# sch_power.net
KiCad netlist of a schematic drawn in Altium Designer
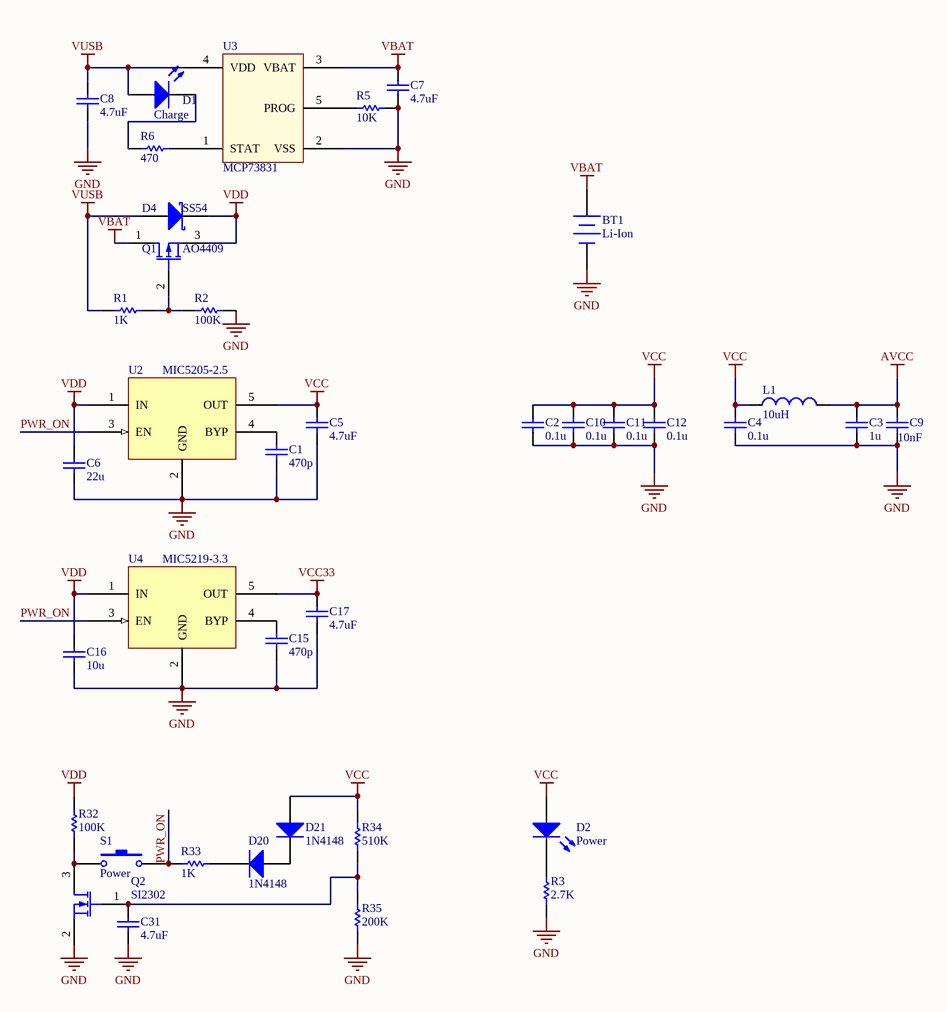
[diagram p0: sch_power.SchDoc]

(export (version "E")
  (design (tool "Eeschema 10.0.6"))
  (components
    (comp (ref "BT1")
      (value "Li-Ion")
      (footprint "HDR1X2")
      (description "Multicell Battery")
      (fields (field (name "PUBLISHER") "Altium Limited"))
      (libsource (lib "Miscellaneous Devices") (part "Battery"))
    )
    (comp (ref "C1")
      (value "470p")
      (footprint "C-1608[0603]")
      (description "Capacitor (Semiconductor SIM Model)")
      (fields (field (name "Comment") "Cap Semi") (field (name "PUBLISHER") "Altium Limited"))
      (libsource (lib "Miscellaneous Devices") (part "Cap Semi"))
    )
    (comp (ref "C2")
      (value "0.1u")
      (footprint "C-1608[0603]")
      (description "Capacitor (Semiconductor SIM Model)")
      (fields (field (name "Comment") "Cap Semi") (field (name "PUBLISHER") "Altium Limited"))
      (libsource (lib "Miscellaneous Devices") (part "Cap Semi"))
    )
    (comp (ref "C3")
      (value "1u")
      (footprint "C-1608[0603]")
      (description "Capacitor (Semiconductor SIM Model)")
      (fields (field (name "Comment") "Cap Semi") (field (name "PUBLISHER") "Altium Limited"))
      (libsource (lib "Miscellaneous Devices") (part "Cap Semi"))
    )
    (comp (ref "C4")
      (value "0.1u")
      (footprint "C-1608[0603]")
      (description "Capacitor (Semiconductor SIM Model)")
      (fields (field (name "Comment") "Cap Semi") (field (name "PUBLISHER") "Altium Limited"))
      (libsource (lib "Miscellaneous Devices") (part "Cap Semi"))
    )
    (comp (ref "C5")
      (value "4.7uF")
      (footprint "C-1608[0603]")
      (description "Capacitor (Semiconductor SIM Model)")
      (fields (field (name "Comment") "Cap Semi") (field (name "PUBLISHER") "Altium Limited"))
      (libsource (lib "Miscellaneous Devices") (part "Cap Semi"))
    )
    (comp (ref "C6")
      (value "22u")
      (footprint "C-2012[0805]")
      (description "Capacitor (Semiconductor SIM Model)")
      (fields (field (name "Comment") "Cap Semi") (field (name "PUBLISHER") "Altium Limited"))
      (libsource (lib "Miscellaneous Devices") (part "Cap Semi"))
    )
    (comp (ref "C7")
      (value "4.7uF")
      (footprint "C-1608[0603]")
      (description "Capacitor (Semiconductor SIM Model)")
      (fields (field (name "Comment") "Cap Semi") (field (name "PUBLISHER") "Altium Limited"))
      (libsource (lib "Miscellaneous Devices") (part "Cap Semi"))
    )
    (comp (ref "C8")
      (value "4.7uF")
      (footprint "C-1608[0603]")
      (description "Capacitor (Semiconductor SIM Model)")
      (fields (field (name "Comment") "Cap Semi") (field (name "PUBLISHER") "Altium Limited"))
      (libsource (lib "Miscellaneous Devices") (part "Cap Semi"))
    )
    (comp (ref "C9")
      (value "10nF")
      (footprint "C-1608[0603]")
      (description "Capacitor (Semiconductor SIM Model)")
      (fields (field (name "Comment") "Cap Semi") (field (name "PUBLISHER") "Altium Limited"))
      (libsource (lib "Miscellaneous Devices") (part "Cap Semi"))
    )
    (comp (ref "C10")
      (value "0.1u")
      (footprint "C-1608[0603]")
      (description "Capacitor (Semiconductor SIM Model)")
      (fields (field (name "Comment") "Cap Semi") (field (name "PUBLISHER") "Altium Limited"))
      (libsource (lib "Miscellaneous Devices") (part "Cap Semi"))
    )
    (comp (ref "C11")
      (value "0.1u")
      (footprint "C-1608[0603]")
      (description "Capacitor (Semiconductor SIM Model)")
      (fields (field (name "Comment") "Cap Semi") (field (name "PUBLISHER") "Altium Limited"))
      (libsource (lib "Miscellaneous Devices") (part "Cap Semi"))
    )
    (comp (ref "C12")
      (value "0.1u")
      (footprint "C-1608[0603]")
      (description "Capacitor (Semiconductor SIM Model)")
      (fields (field (name "Comment") "Cap Semi") (field (name "PUBLISHER") "Altium Limited"))
      (libsource (lib "Miscellaneous Devices") (part "Cap Semi"))
    )
    (comp (ref "C15")
      (value "470p")
      (footprint "C-1608[0603]")
      (description "Capacitor (Semiconductor SIM Model)")
      (fields (field (name "Comment") "Cap Semi") (field (name "PUBLISHER") "Altium Limited"))
      (libsource (lib "Miscellaneous Devices") (part "Cap Semi"))
    )
    (comp (ref "C16")
      (value "10u")
      (footprint "C-2012[0805]")
      (description "Capacitor (Semiconductor SIM Model)")
      (fields (field (name "Comment") "Cap Semi") (field (name "PUBLISHER") "Altium Limited"))
      (libsource (lib "Miscellaneous Devices") (part "Cap Semi"))
    )
    (comp (ref "C17")
      (value "4.7uF")
      (footprint "C-1608[0603]")
      (description "Capacitor (Semiconductor SIM Model)")
      (fields (field (name "Comment") "Cap Semi") (field (name "PUBLISHER") "Altium Limited"))
      (libsource (lib "Miscellaneous Devices") (part "Cap Semi"))
    )
    (comp (ref "C31")
      (value "4.7uF")
      (footprint "C-1608[0603]")
      (description "Capacitor (Semiconductor SIM Model)")
      (fields (field (name "Comment") "Cap Semi") (field (name "PUBLISHER") "Altium Limited"))
      (libsource (lib "Miscellaneous Devices") (part "Cap Semi"))
    )
    (comp (ref "D1")
      (value "Charge")
      (footprint "LED-1608[0603]-R")
      (description "Typical RED, GREEN, YELLOW, AMBER GaAs LED")
      (fields (field (name "PUBLISHER") "Altium Limited"))
      (libsource (lib "Miscellaneous Devices") (part "LED2"))
    )
    (comp (ref "D2")
      (value "Power")
      (footprint "LED-1608[0603]-G")
      (description "Typical RED, GREEN, YELLOW, AMBER GaAs LED")
      (fields (field (name "PUBLISHER") "Altium Limited"))
      (libsource (lib "Miscellaneous Devices") (part "LED2"))
    )
    (comp (ref "D4")
      (value "SS54")
      (footprint "general:DO-214AA")
      (description "Schottky Diode")
      (fields (field (name "PUBLISHER") "Altium Limited"))
      (libsource (lib "Miscellaneous Devices") (part "D Schottky"))
    )
    (comp (ref "D20")
      (value "1N4148")
      (footprint "SOD80C")
      (description "High Conductance Fast Diode")
      (fields (field (name "PUBLISHER") "Altium Limited"))
      (libsource (lib "Miscellaneous Devices") (part "Diode 1N4148"))
    )
    (comp (ref "D21")
      (value "1N4148")
      (footprint "SOD80C")
      (description "High Conductance Fast Diode")
      (fields (field (name "PUBLISHER") "Altium Limited"))
      (libsource (lib "Miscellaneous Devices") (part "Diode 1N4148"))
    )
    (comp (ref "L1")
      (value "10uH")
      (footprint "L-1608[0603]")
      (description "Inductor")
      (fields (field (name "PUBLISHER") "Altium Limited"))
      (libsource (lib "Miscellaneous Devices") (part "Inductor"))
    )
    (comp (ref "Q1")
      (value "AO4409")
      (footprint "SOP8-MOS")
      (description "P-Channel MOSFET")
      (fields (field (name "PUBLISHER") "Altium Limited"))
      (libsource (lib "Miscellaneous Devices") (part "MOSFET-P"))
    )
    (comp (ref "Q2")
      (value "SI2302")
      (footprint "SOT23B")
      (description "N-Channel MOSFET")
      (fields (field (name "PUBLISHER") "Altium Limited"))
      (libsource (lib "general") (part "SI2302"))
    )
    (comp (ref "R1")
      (value "1K")
      (footprint "R-1608[0603]")
      (description "Semiconductor Resistor")
      (fields (field (name "Comment") "Res Semi") (field (name "PUBLISHER") "Altium Limited"))
      (libsource (lib "Miscellaneous Devices") (part "Res Semi"))
    )
    (comp (ref "R2")
      (value "100K")
      (footprint "R-1608[0603]")
      (description "Semiconductor Resistor")
      (fields (field (name "Comment") "Res Semi") (field (name "PUBLISHER") "Altium Limited"))
      (libsource (lib "Miscellaneous Devices") (part "Res Semi"))
    )
    (comp (ref "R3")
      (value "2.7K")
      (footprint "R-1608[0603]")
      (description "Semiconductor Resistor")
      (fields (field (name "Comment") "Res Semi") (field (name "PUBLISHER") "Altium Limited"))
      (libsource (lib "Miscellaneous Devices") (part "Res Semi"))
    )
    (comp (ref "R5")
      (value "10K")
      (footprint "R-1608[0603]")
      (description "Semiconductor Resistor")
      (fields (field (name "Comment") "Res Semi") (field (name "PUBLISHER") "Altium Limited"))
      (libsource (lib "Miscellaneous Devices") (part "Res Semi"))
    )
    (comp (ref "R6")
      (value "470")
      (footprint "R-1608[0603]")
      (description "Semiconductor Resistor")
      (fields (field (name "Comment") "Res Semi") (field (name "PUBLISHER") "Altium Limited"))
      (libsource (lib "Miscellaneous Devices") (part "Res Semi"))
    )
    (comp (ref "R32")
      (value "100K")
      (footprint "R-1608[0603]")
      (description "Semiconductor Resistor")
      (fields (field (name "Comment") "Res Semi") (field (name "PUBLISHER") "Altium Limited"))
      (libsource (lib "Miscellaneous Devices") (part "Res Semi"))
    )
    (comp (ref "R33")
      (value "1K")
      (footprint "R-1608[0603]")
      (description "Semiconductor Resistor")
      (fields (field (name "Comment") "Res Semi") (field (name "PUBLISHER") "Altium Limited"))
      (libsource (lib "Miscellaneous Devices") (part "Res Semi"))
    )
    (comp (ref "R34")
      (value "510K")
      (footprint "R-1608[0603]")
      (description "Semiconductor Resistor")
      (fields (field (name "Comment") "Res Semi") (field (name "PUBLISHER") "Altium Limited"))
      (libsource (lib "Miscellaneous Devices") (part "Res Semi"))
    )
    (comp (ref "R35")
      (value "200K")
      (footprint "R-1608[0603]")
      (description "Semiconductor Resistor")
      (fields (field (name "Comment") "Res Semi") (field (name "PUBLISHER") "Altium Limited"))
      (libsource (lib "Miscellaneous Devices") (part "Res Semi"))
    )
    (comp (ref "S1")
      (value "Power")
      (footprint "TS-015")
      (description "Switch")
      (fields (field (name "PUBLISHER") "Altium Limited"))
      (libsource (lib "Miscellaneous Devices") (part "SW-PB"))
    )
    (comp (ref "U2")
      (value "MIC5205-2.5")
      (footprint "SOT23-5")
      (description "500mA-Peak Output LDO Regulator")
      (libsource (lib "Schlib1") (part "MIC5219"))
    )
    (comp (ref "U3")
      (value "MCP73831")
      (footprint "SOT23-5")
      (description "Miniature Single-Cell, Fully Integrated Li-Ion, Li-Polymer Charge Management Controllers")
      (libsource (lib "MCP73831") (part "MCP73831"))
    )
    (comp (ref "U4")
      (value "MIC5219-3.3")
      (footprint "SOT23-5")
      (description "500mA-Peak Output LDO Regulator")
      (libsource (lib "Schlib1") (part "MIC5219"))
    )
  )
  (nets
    (net (code "1") (name "/PWR_ON") (class "Default")
      (node (ref "R33") (pin "2") (pinfunction "2_2") (pintype "passive"))
      (node (ref "S1") (pin "2") (pinfunction "2_2") (pintype "passive"))
      (node (ref "U2") (pin "3") (pinfunction "EN_3") (pintype "input"))
      (node (ref "U4") (pin "3") (pinfunction "EN_3") (pintype "input"))
    )
    (net (code "2") (name "AVCC") (class "Default")
      (node (ref "C3") (pin "2") (pinfunction "2_2") (pintype "passive"))
      (node (ref "C9") (pin "2") (pinfunction "2_2") (pintype "passive"))
      (node (ref "L1") (pin "2") (pinfunction "2_2") (pintype "passive"))
    )
    (net (code "3") (name "GND") (class "Default")
      (node (ref "BT1") (pin "2") (pinfunction "-_2") (pintype "passive"))
      (node (ref "C1") (pin "2") (pinfunction "2_2") (pintype "passive"))
      (node (ref "C10") (pin "1") (pinfunction "1_1") (pintype "passive"))
      (node (ref "C11") (pin "1") (pinfunction "1_1") (pintype "passive"))
      (node (ref "C12") (pin "1") (pinfunction "1_1") (pintype "passive"))
      (node (ref "C15") (pin "2") (pinfunction "2_2") (pintype "passive"))
      (node (ref "C16") (pin "2") (pinfunction "2_2") (pintype "passive"))
      (node (ref "C17") (pin "2") (pinfunction "2_2") (pintype "passive"))
      (node (ref "C2") (pin "1") (pinfunction "1_1") (pintype "passive"))
      (node (ref "C3") (pin "1") (pinfunction "1_1") (pintype "passive"))
      (node (ref "C31") (pin "1") (pinfunction "1_1") (pintype "passive"))
      (node (ref "C4") (pin "1") (pinfunction "1_1") (pintype "passive"))
      (node (ref "C5") (pin "2") (pinfunction "2_2") (pintype "passive"))
      (node (ref "C6") (pin "2") (pinfunction "2_2") (pintype "passive"))
      (node (ref "C7") (pin "1") (pinfunction "1_1") (pintype "passive"))
      (node (ref "C8") (pin "1") (pinfunction "1_1") (pintype "passive"))
      (node (ref "C9") (pin "1") (pinfunction "1_1") (pintype "passive"))
      (node (ref "Q2") (pin "2") (pinfunction "S_2") (pintype "passive"))
      (node (ref "R2") (pin "2") (pinfunction "2_2") (pintype "passive"))
      (node (ref "R3") (pin "2") (pinfunction "2_2") (pintype "passive"))
      (node (ref "R35") (pin "1") (pinfunction "1_1") (pintype "passive"))
      (node (ref "R5") (pin "1") (pinfunction "1_1") (pintype "passive"))
      (node (ref "U2") (pin "2") (pinfunction "GND_2") (pintype "passive"))
      (node (ref "U3") (pin "2") (pinfunction "VSS_2") (pintype "passive"))
      (node (ref "U4") (pin "2") (pinfunction "GND_2") (pintype "passive"))
    )
    (net (code "4") (name "Net-(D1-K)") (class "Default")
      (node (ref "D1") (pin "2") (pinfunction "K_2") (pintype "passive"))
      (node (ref "R6") (pin "1") (pinfunction "1_1") (pintype "passive"))
    )
    (net (code "5") (name "Net-(D2-K)") (class "Default")
      (node (ref "D2") (pin "2") (pinfunction "K_2") (pintype "passive"))
      (node (ref "R3") (pin "1") (pinfunction "1_1") (pintype "passive"))
    )
    (net (code "6") (name "Net-(D20-A)") (class "Default")
      (node (ref "D20") (pin "1") (pinfunction "A_1") (pintype "passive"))
      (node (ref "D21") (pin "2") (pinfunction "K_2") (pintype "passive"))
    )
    (net (code "7") (name "Net-(D20-K)") (class "Default")
      (node (ref "D20") (pin "2") (pinfunction "K_2") (pintype "passive"))
      (node (ref "R33") (pin "1") (pinfunction "1_1") (pintype "passive"))
    )
    (net (code "8") (name "Net-(Q1-G)") (class "Default")
      (node (ref "Q1") (pin "2") (pinfunction "G_2") (pintype "passive"))
      (node (ref "R1") (pin "2") (pinfunction "2_2") (pintype "passive"))
      (node (ref "R2") (pin "1") (pinfunction "1_1") (pintype "passive"))
    )
    (net (code "9") (name "Net-(Q2-D)") (class "Default")
      (node (ref "Q2") (pin "3") (pinfunction "D_3") (pintype "passive"))
      (node (ref "R32") (pin "1") (pinfunction "1_1") (pintype "passive"))
      (node (ref "S1") (pin "1") (pinfunction "1_1") (pintype "passive"))
    )
    (net (code "10") (name "Net-(Q2-G)") (class "Default")
      (node (ref "C31") (pin "2") (pinfunction "2_2") (pintype "passive"))
      (node (ref "Q2") (pin "1") (pinfunction "G_1") (pintype "passive"))
      (node (ref "R34") (pin "1") (pinfunction "1_1") (pintype "passive"))
      (node (ref "R35") (pin "2") (pinfunction "2_2") (pintype "passive"))
    )
    (net (code "11") (name "Net-(U2-BYP)") (class "Default")
      (node (ref "C1") (pin "1") (pinfunction "1_1") (pintype "passive"))
      (node (ref "U2") (pin "4") (pinfunction "BYP_4") (pintype "passive"))
    )
    (net (code "12") (name "Net-(U3-PROG)") (class "Default")
      (node (ref "R5") (pin "2") (pinfunction "2_2") (pintype "passive"))
      (node (ref "U3") (pin "5") (pinfunction "PROG_5") (pintype "passive"))
    )
    (net (code "13") (name "Net-(U3-STAT)") (class "Default")
      (node (ref "R6") (pin "2") (pinfunction "2_2") (pintype "passive"))
      (node (ref "U3") (pin "1") (pinfunction "STAT_1") (pintype "passive"))
    )
    (net (code "14") (name "Net-(U4-BYP)") (class "Default")
      (node (ref "C15") (pin "1") (pinfunction "1_1") (pintype "passive"))
      (node (ref "U4") (pin "4") (pinfunction "BYP_4") (pintype "passive"))
    )
    (net (code "15") (name "VBAT") (class "Default")
      (node (ref "BT1") (pin "1") (pinfunction "+_1") (pintype "passive"))
      (node (ref "C7") (pin "2") (pinfunction "2_2") (pintype "passive"))
      (node (ref "Q1") (pin "1") (pinfunction "D_1") (pintype "passive"))
      (node (ref "U3") (pin "3") (pinfunction "VBAT_3") (pintype "passive"))
    )
    (net (code "16") (name "VCC") (class "Default")
      (node (ref "C10") (pin "2") (pinfunction "2_2") (pintype "passive"))
      (node (ref "C11") (pin "2") (pinfunction "2_2") (pintype "passive"))
      (node (ref "C12") (pin "2") (pinfunction "2_2") (pintype "passive"))
      (node (ref "C2") (pin "2") (pinfunction "2_2") (pintype "passive"))
      (node (ref "C4") (pin "2") (pinfunction "2_2") (pintype "passive"))
      (node (ref "C5") (pin "1") (pinfunction "1_1") (pintype "passive"))
      (node (ref "D2") (pin "1") (pinfunction "A_1") (pintype "passive"))
      (node (ref "D21") (pin "1") (pinfunction "A_1") (pintype "passive"))
      (node (ref "L1") (pin "1") (pinfunction "1_1") (pintype "passive"))
      (node (ref "R34") (pin "2") (pinfunction "2_2") (pintype "passive"))
      (node (ref "U2") (pin "5") (pinfunction "OUT_5") (pintype "passive"))
    )
    (net (code "17") (name "VCC33") (class "Default")
      (node (ref "C17") (pin "1") (pinfunction "1_1") (pintype "passive"))
      (node (ref "U4") (pin "5") (pinfunction "OUT_5") (pintype "passive"))
    )
    (net (code "18") (name "VDD") (class "Default")
      (node (ref "C16") (pin "1") (pinfunction "1_1") (pintype "passive"))
      (node (ref "C6") (pin "1") (pinfunction "1_1") (pintype "passive"))
      (node (ref "D4") (pin "2") (pinfunction "K_2") (pintype "passive"))
      (node (ref "Q1") (pin "3") (pinfunction "S_3") (pintype "passive"))
      (node (ref "R32") (pin "2") (pinfunction "2_2") (pintype "passive"))
      (node (ref "U2") (pin "1") (pinfunction "IN_1") (pintype "power_in"))
      (node (ref "U4") (pin "1") (pinfunction "IN_1") (pintype "power_in"))
    )
    (net (code "19") (name "VUSB") (class "Default")
      (node (ref "C8") (pin "2") (pinfunction "2_2") (pintype "passive"))
      (node (ref "D1") (pin "1") (pinfunction "A_1") (pintype "passive"))
      (node (ref "D4") (pin "1") (pinfunction "A_1") (pintype "passive"))
      (node (ref "R1") (pin "1") (pinfunction "1_1") (pintype "passive"))
      (node (ref "U3") (pin "4") (pinfunction "VDD_4") (pintype "passive"))
    )
  )
)
